# DigiPC_Jr.net
KiCad netlist of a schematic drawn in EAGLE
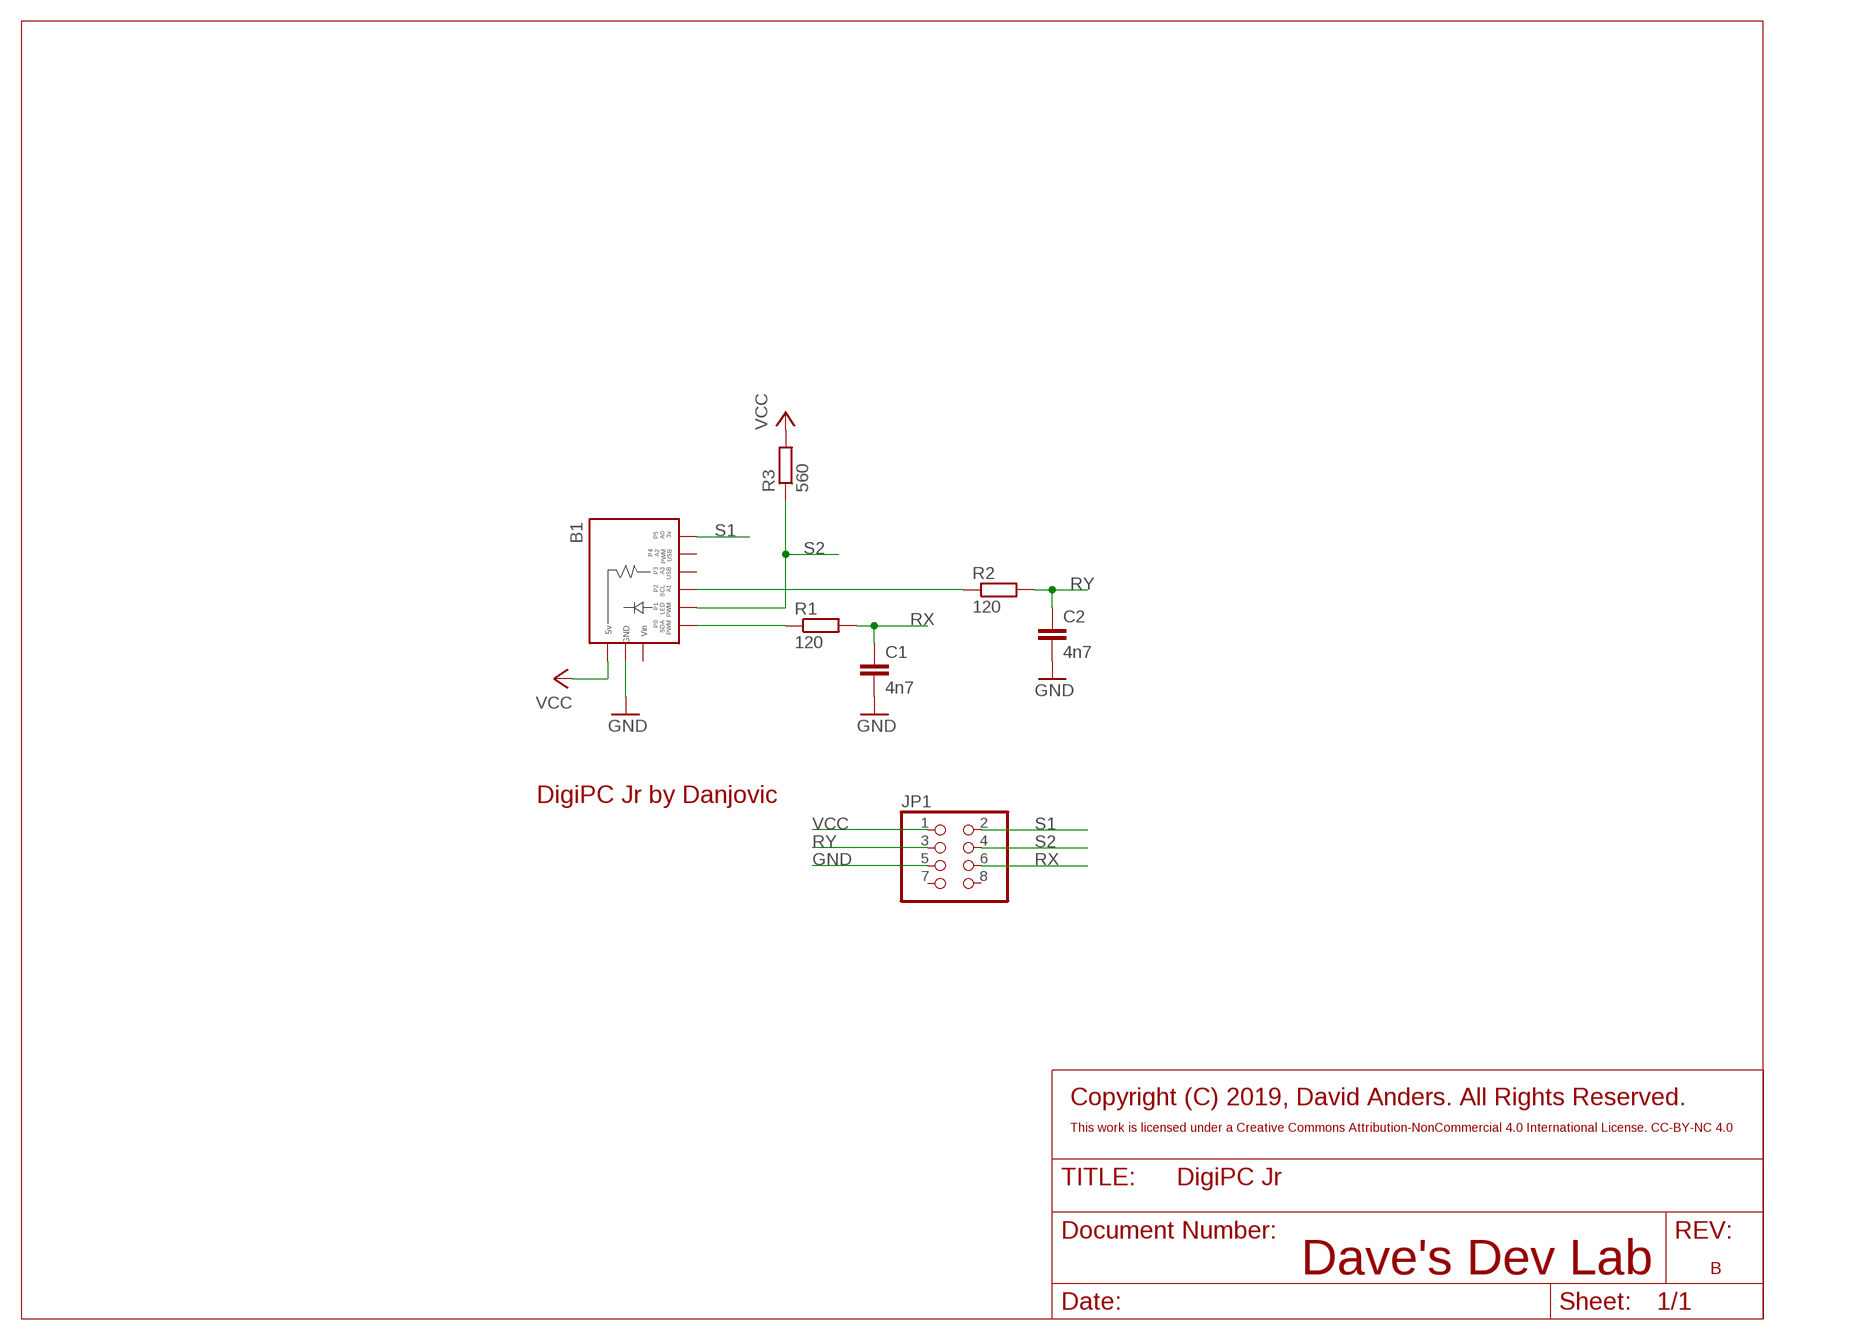
[diagram p0: schematic, sheet 1]

(export (version "E")
  (design (tool "Eeschema 10.0.6"))
  (components
    (comp (ref "B1")
      (value "DIGISPARK-SOCKET")
      (footprint "eagle-import:DIGISPARK_SOCKET")
      (libsource (lib "eagle-import") (part "DIGISPARK-SOCKET"))
    )
    (comp (ref "C1")
      (value "4n7")
      (footprint "eagle-import:C050-024X044")
      (libsource (lib "eagle-import") (part "C-EU050-024X044"))
    )
    (comp (ref "C2")
      (value "4n7")
      (footprint "eagle-import:C050-024X044")
      (libsource (lib "eagle-import") (part "C-EU050-024X044"))
    )
    (comp (ref "JP1")
      (value "PINHD-2X4/90")
      (footprint "eagle-import:2X04_90")
      (libsource (lib "eagle-import") (part "PINHD-2X4/90"))
    )
    (comp (ref "R1")
      (value "120")
      (footprint "eagle-import:0204_7")
      (libsource (lib "eagle-import") (part "R-EU_0204/7"))
    )
    (comp (ref "R2")
      (value "120")
      (footprint "eagle-import:0204_7")
      (libsource (lib "eagle-import") (part "R-EU_0204/7"))
    )
    (comp (ref "R3")
      (value "560")
      (footprint "eagle-import:0204_7")
      (libsource (lib "eagle-import") (part "R-EU_0204/7"))
    )
  )
  (nets
    (net (code "1") (name "/RX") (class "Default")
      (node (ref "C1") (pin "1") (pinfunction "1_1") (pintype "passive"))
      (node (ref "JP1") (pin "6") (pinfunction "6_6") (pintype "passive"))
      (node (ref "R1") (pin "2") (pinfunction "2_2") (pintype "passive"))
    )
    (net (code "2") (name "/RY") (class "Default")
      (node (ref "C2") (pin "1") (pinfunction "1_1") (pintype "passive"))
      (node (ref "JP1") (pin "3") (pinfunction "3_3") (pintype "passive"))
      (node (ref "R2") (pin "2") (pinfunction "2_2") (pintype "passive"))
    )
    (net (code "3") (name "/S1") (class "Default")
      (node (ref "B1") (pin "P5") (pinfunction "P5_P5") (pintype "bidirectional"))
      (node (ref "JP1") (pin "2") (pinfunction "2_2") (pintype "passive"))
    )
    (net (code "4") (name "/S2") (class "Default")
      (node (ref "B1") (pin "P1") (pinfunction "P1_P1") (pintype "bidirectional"))
      (node (ref "JP1") (pin "4") (pinfunction "4_4") (pintype "passive"))
      (node (ref "R3") (pin "1") (pinfunction "1_1") (pintype "passive"))
    )
    (net (code "5") (name "/VIN") (class "Default")
      (node (ref "B1") (pin "VIN") (pinfunction "VIN_VIN") (pintype "power_in"))
    )
    (net (code "6") (name "GND") (class "Default")
      (node (ref "B1") (pin "GND") (pinfunction "GND_GND") (pintype "power_in"))
      (node (ref "C1") (pin "2") (pinfunction "2_2") (pintype "passive"))
      (node (ref "C2") (pin "2") (pinfunction "2_2") (pintype "passive"))
      (node (ref "JP1") (pin "5") (pinfunction "5_5") (pintype "passive"))
    )
    (net (code "7") (name "Net-(B1-PadP0)") (class "Default")
      (node (ref "B1") (pin "P0") (pinfunction "P0_P0") (pintype "bidirectional"))
      (node (ref "R1") (pin "1") (pinfunction "1_1") (pintype "passive"))
    )
    (net (code "8") (name "Net-(B1-PadP2)") (class "Default")
      (node (ref "B1") (pin "P2") (pinfunction "P2_P2") (pintype "bidirectional"))
      (node (ref "R2") (pin "1") (pinfunction "1_1") (pintype "passive"))
    )
    (net (code "9") (name "VCC") (class "Default")
      (node (ref "B1") (pin "5V") (pinfunction "5V_5V") (pintype "power_in"))
      (node (ref "JP1") (pin "1") (pinfunction "1_1") (pintype "passive"))
      (node (ref "R3") (pin "2") (pinfunction "2_2") (pintype "passive"))
    )
    (net (code "10") (name "unconnected-(B1-PadP3)") (class "Default")
      (node (ref "B1") (pin "P3") (pinfunction "P3_P3") (pintype "bidirectional"))
    )
    (net (code "11") (name "unconnected-(B1-PadP4)") (class "Default")
      (node (ref "B1") (pin "P4") (pinfunction "P4_P4") (pintype "bidirectional"))
    )
    (net (code "12") (name "unconnected-(JP1-Pad7)") (class "Default")
      (node (ref "JP1") (pin "7") (pinfunction "7_7") (pintype "passive"))
    )
    (net (code "13") (name "unconnected-(JP1-Pad8)") (class "Default")
      (node (ref "JP1") (pin "8") (pinfunction "8_8") (pintype "passive"))
    )
  )
)
